# TactA.net
KiCad netlist of a schematic drawn in EAGLE
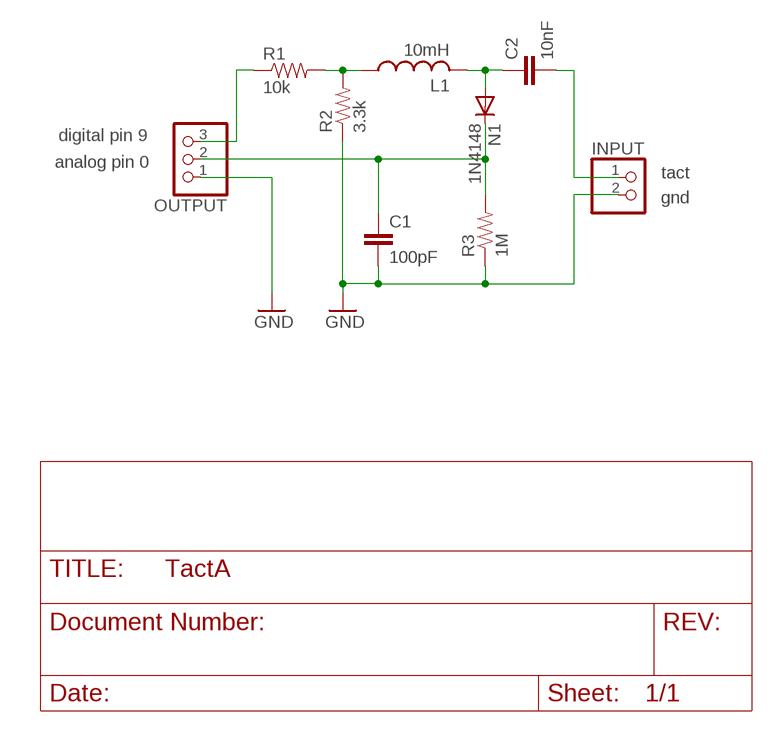
[diagram p0: schematic, sheet 1]

(export (version "E")
  (design (tool "Eeschema 10.0.6"))
  (components
    (comp (ref "C1")
      (value "100pF")
      (footprint "eagle-import:CAP-PTH-SMALL")
      (libsource (lib "eagle-import") (part "CAPPTH"))
    )
    (comp (ref "C2")
      (value "10nF")
      (footprint "eagle-import:CAP-PTH-SMALL")
      (libsource (lib "eagle-import") (part "CAPPTH"))
    )
    (comp (ref "INPUT")
      (value "PINHD-1X2")
      (footprint "eagle-import:1X02")
      (libsource (lib "eagle-import") (part "PINHD-1X2"))
    )
    (comp (ref "L1")
      (value "10mH")
      (footprint "eagle-import:6000-XXXX-RC")
      (libsource (lib "eagle-import") (part "L-US6000-XXX-RC"))
    )
    (comp (ref "N1")
      (value "1N4148")
      (footprint "eagle-import:DO35-7")
      (libsource (lib "eagle-import") (part "1N4148DO35-7"))
    )
    (comp (ref "OUTPUT")
      (value "PINHD-1X3")
      (footprint "eagle-import:1X03")
      (libsource (lib "eagle-import") (part "PINHD-1X3"))
    )
    (comp (ref "R1")
      (value "10k")
      (footprint "eagle-import:AXIAL-0.4")
      (libsource (lib "eagle-import") (part "RESISTORPTH-1/4W"))
    )
    (comp (ref "R2")
      (value "3.3k")
      (footprint "eagle-import:AXIAL-0.4")
      (libsource (lib "eagle-import") (part "RESISTORPTH-1/4W"))
    )
    (comp (ref "R3")
      (value "1M")
      (footprint "eagle-import:AXIAL-0.4")
      (libsource (lib "eagle-import") (part "RESISTORPTH-1/4W"))
    )
  )
  (nets
    (net (code "1") (name "GND") (class "Default")
      (node (ref "C1") (pin "2") (pinfunction "2_2") (pintype "passive"))
      (node (ref "INPUT") (pin "2") (pinfunction "2_2") (pintype "passive"))
      (node (ref "OUTPUT") (pin "1") (pinfunction "1_1") (pintype "passive"))
      (node (ref "R2") (pin "P$1") (pinfunction "1_P$1") (pintype "passive"))
      (node (ref "R3") (pin "P$1") (pinfunction "1_P$1") (pintype "passive"))
    )
    (net (code "2") (name "Net-(C2-Pad1)") (class "Default")
      (node (ref "C2") (pin "1") (pinfunction "1_1") (pintype "passive"))
      (node (ref "L1") (pin "2") (pinfunction "2_2") (pintype "passive"))
      (node (ref "N1") (pin "A") (pinfunction "A_A") (pintype "passive"))
    )
    (net (code "3") (name "Net-(C2-Pad2)") (class "Default")
      (node (ref "C2") (pin "2") (pinfunction "2_2") (pintype "passive"))
      (node (ref "INPUT") (pin "1") (pinfunction "1_1") (pintype "passive"))
    )
    (net (code "4") (name "Net-(R1-1)") (class "Default")
      (node (ref "OUTPUT") (pin "3") (pinfunction "3_3") (pintype "passive"))
      (node (ref "R1") (pin "P$1") (pinfunction "1_P$1") (pintype "passive"))
    )
    (net (code "5") (name "Net-(R1-2)") (class "Default")
      (node (ref "L1") (pin "1") (pinfunction "1_1") (pintype "passive"))
      (node (ref "R1") (pin "P$2") (pinfunction "2_P$2") (pintype "passive"))
      (node (ref "R2") (pin "P$2") (pinfunction "2_P$2") (pintype "passive"))
    )
    (net (code "6") (name "Net-(R3-2)") (class "Default")
      (node (ref "C1") (pin "1") (pinfunction "1_1") (pintype "passive"))
      (node (ref "N1") (pin "C") (pinfunction "C_C") (pintype "passive"))
      (node (ref "OUTPUT") (pin "2") (pinfunction "2_2") (pintype "passive"))
      (node (ref "R3") (pin "P$2") (pinfunction "2_P$2") (pintype "passive"))
    )
  )
)
